# Main.net
KiCad netlist of a schematic drawn in Altium Designer
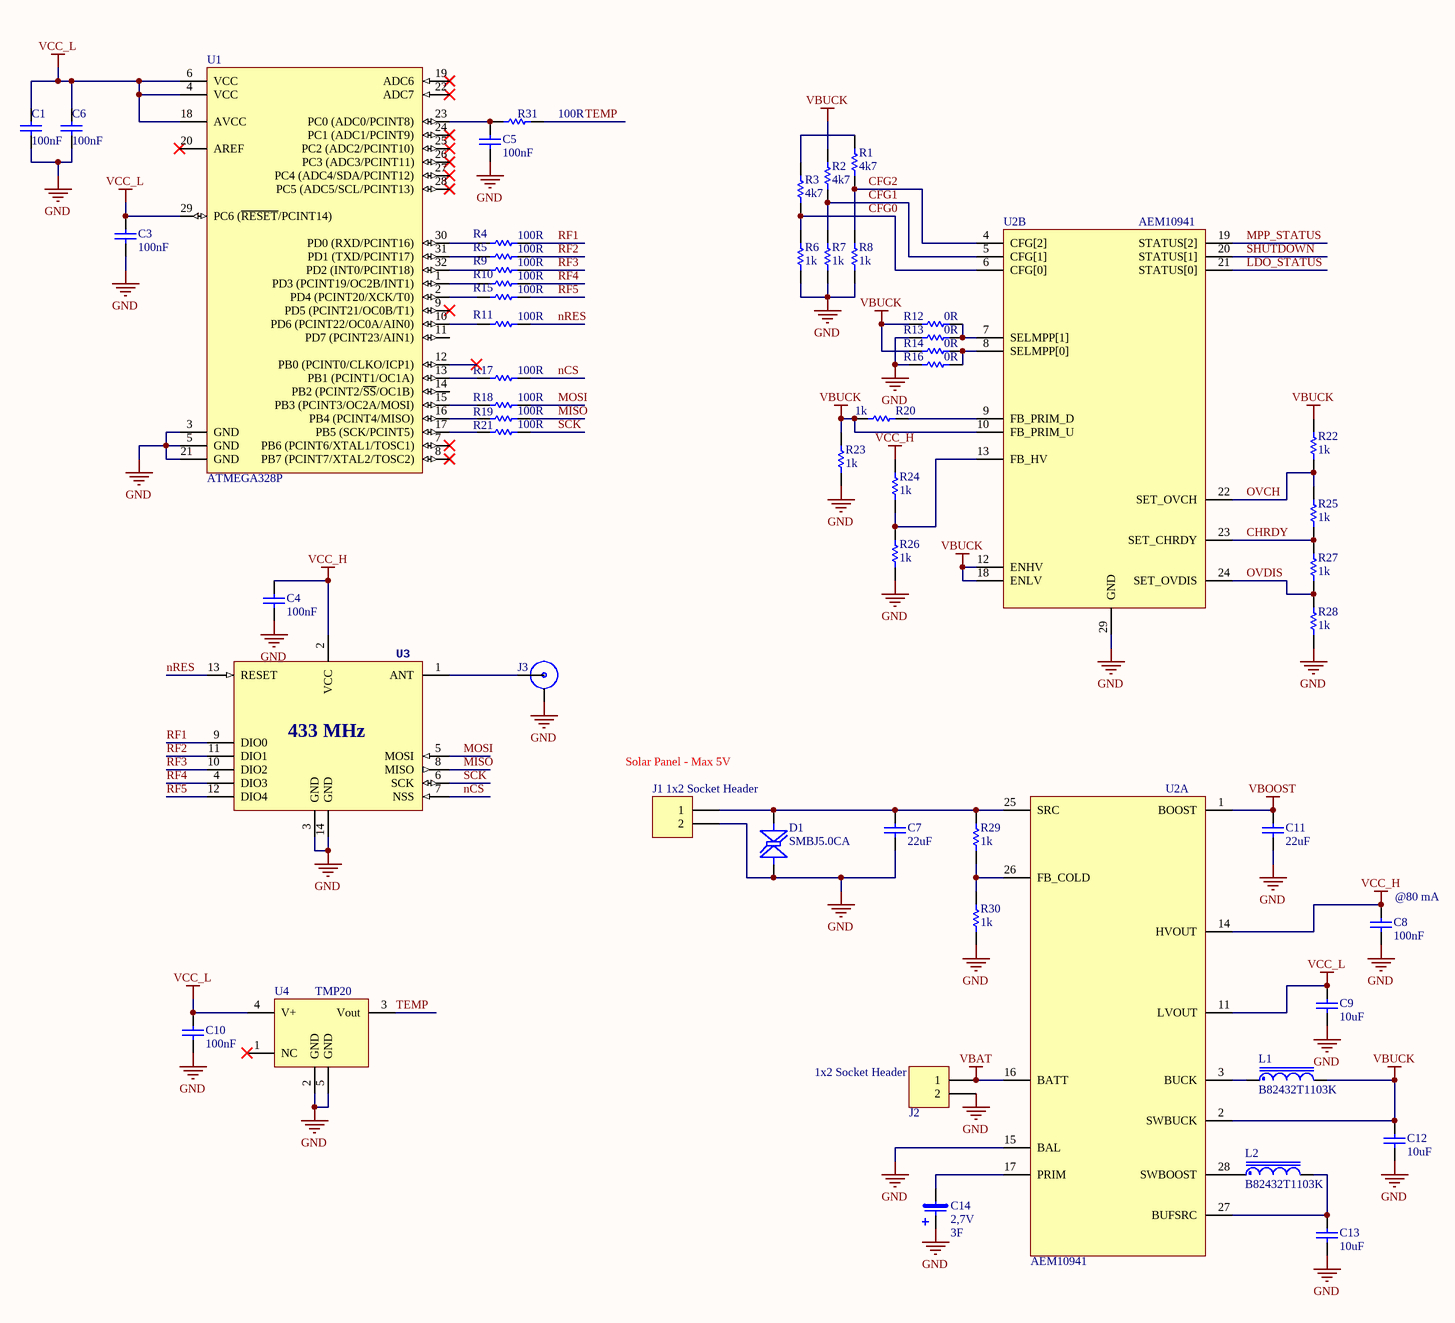
[diagram p0: Main.SchDoc]

(export (version "E")
  (design (tool "Eeschema 10.0.6"))
  (components
    (comp (ref "C1")
      (value "100nF")
      (footprint "C0603")
      (description "Capacitor SMD")
      (fields (field (name "VOLTAGE") "16V") (field (name "PART NUMBER") "C0603_100nF_16V_±10%"))
      (libsource (lib "Pasives_Capacitor_SMD") (part "Capacitor"))
    )
    (comp (ref "C3")
      (value "100nF")
      (footprint "C0603")
      (description "Capacitor SMD")
      (fields (field (name "VOLTAGE") "16V") (field (name "PART NUMBER") "C0603_100nF_16V_±10%"))
      (libsource (lib "Pasives_Capacitor_SMD") (part "Capacitor"))
    )
    (comp (ref "C4")
      (value "100nF")
      (footprint "C0603")
      (description "Capacitor SMD")
      (fields (field (name "VOLTAGE") "16V") (field (name "PART NUMBER") "C0603_100nF_16V_±10%"))
      (libsource (lib "Pasives_Capacitor_SMD") (part "Capacitor"))
    )
    (comp (ref "C5")
      (value "100nF")
      (footprint "C0603")
      (description "Capacitor SMD")
      (fields (field (name "VOLTAGE") "16V") (field (name "PART NUMBER") "C0603_100nF_16V_±10%"))
      (libsource (lib "Pasives_Capacitor_SMD") (part "Capacitor"))
    )
    (comp (ref "C6")
      (value "100nF")
      (footprint "C0603")
      (description "Capacitor SMD")
      (fields (field (name "VOLTAGE") "16V") (field (name "PART NUMBER") "C0603_100nF_16V_±10%"))
      (libsource (lib "Pasives_Capacitor_SMD") (part "Capacitor"))
    )
    (comp (ref "C7")
      (value "22uF")
      (footprint "C1206")
      (description "Capacitor SMD")
      (fields (field (name "VOLTAGE") "10V") (field (name "PART NUMBER") "C1206_22uF_10V_±10%"))
      (libsource (lib "Pasives_Capacitor_SMD") (part "Capacitor"))
    )
    (comp (ref "C8")
      (value "100nF")
      (footprint "C0603")
      (description "Capacitor SMD")
      (fields (field (name "VOLTAGE") "16V") (field (name "PART NUMBER") "C0603_100nF_16V_±10%"))
      (libsource (lib "Pasives_Capacitor_SMD") (part "Capacitor"))
    )
    (comp (ref "C9")
      (value "10uF")
      (footprint "C1206")
      (description "Capacitor SMD")
      (fields (field (name "VOLTAGE") "25V") (field (name "PART NUMBER") "C1206_10uF_25V_±10%"))
      (libsource (lib "Pasives_Capacitor_SMD") (part "Capacitor"))
    )
    (comp (ref "C10")
      (value "100nF")
      (footprint "C0603")
      (description "Capacitor SMD")
      (fields (field (name "VOLTAGE") "16V") (field (name "PART NUMBER") "C0603_100nF_16V_±10%"))
      (libsource (lib "Pasives_Capacitor_SMD") (part "Capacitor"))
    )
    (comp (ref "C11")
      (value "22uF")
      (footprint "C1206")
      (description "Capacitor SMD")
      (fields (field (name "VOLTAGE") "25V") (field (name "PART NUMBER") "C1206_22uF_25V_±10%"))
      (libsource (lib "Pasives_Capacitor_SMD") (part "Capacitor"))
    )
    (comp (ref "C12")
      (value "10uF")
      (footprint "C1210")
      (description "Capacitor SMD")
      (fields (field (name "VOLTAGE") "50V") (field (name "PART NUMBER") "C1210_10uF_50V_±10%"))
      (libsource (lib "Pasives_Capacitor_SMD") (part "Capacitor"))
    )
    (comp (ref "C13")
      (value "10uF")
      (footprint "C1210")
      (description "Capacitor SMD")
      (fields (field (name "VOLTAGE") "50V") (field (name "PART NUMBER") "C1210_10uF_50V_±10%"))
      (libsource (lib "Pasives_Capacitor_SMD") (part "Capacitor"))
    )
    (comp (ref "C14")
      (value "Electrolytic")
      (footprint "WCAP-STSC_D8xH20mm")
      (description "Capacitor, Electrolytic, THT")
      (fields
        (field (name "VOLTAGE") "2,7V")
        (field (name "CAPACITANCE") "3F")
        (field (name "PART NUMBER") "850617030001")
        (field (name "MANUFACTURER") "Wurth")
      )
      (libsource (lib "Pasives_Electrolytic_THT") (part "Electrolytic"))
    )
    (comp (ref "D1")
      (value "SMBJ5.0CA")
      (footprint "DO-214AA")
      (description "Protection, Bidirectional Transient Suppression Diodes")
      (fields (field (name "PART NUMBER") "TVS Bidir 5Vdc") (field (name "VOLTAGE") "5Vdc"))
      (libsource (lib "Protection") (part "Zener_Bidir_TVS"))
    )
    (comp (ref "J1")
      (value "1x2 Socket Header")
      (footprint "MOLEX 22-05-7025")
      (description "Connector, 2 pin Socket Header")
      (fields (field (name "PART NUMBER") "Molex - 2 pin") (field (name "MANUFACTURER") "Molex"))
      (libsource (lib "Connectors_Power") (part "1x2 Socket Header"))
    )
    (comp (ref "J2")
      (value "1x2 Socket Header")
      (footprint "MOLEX 22-05-7025")
      (description "Connector, 2 pin Socket Header")
      (fields (field (name "PART NUMBER") "Molex - 2 pin") (field (name "MANUFACTURER") "Molex"))
      (libsource (lib "Connectors_Power") (part "1x2 Socket Header"))
    )
    (comp (ref "J3")
      (value "132322")
      (footprint "SMA_Edge_132322")
      (description "Coax")
      (fields (field (name "PART NUMBER") "SMA_Edge_132322") (field (name "MANUFACTURER") "FCI Amphenol"))
      (libsource (lib "Connectors_Antenna") (part "Coax"))
    )
    (comp (ref "L1")
      (value "B82432T1103K")
      (footprint "L1812-T")
      (description "Inductor, Power, SMD")
      (fields (field (name "PART NUMBER") "10uH_0,650A") (field (name "MANUFACTURER") "Epcos"))
      (libsource (lib "Pasivos_Inductor_SMD") (part "Power Inductor"))
    )
    (comp (ref "L2")
      (value "B82432T1103K")
      (footprint "L1812-T")
      (description "Inductor, Power, SMD")
      (fields (field (name "PART NUMBER") "10uH_0,650A") (field (name "MANUFACTURER") "Epcos"))
      (libsource (lib "Pasivos_Inductor_SMD") (part "Power Inductor"))
    )
    (comp (ref "R1")
      (value "4k7")
      (footprint "R0603")
      (description "Resistor, SMD")
      (fields (field (name "TOLERANCE") "±1%") (field (name "POWER") "0.1W"))
      (libsource (lib "Pasives_Resistor_SMD") (part "Resistor"))
    )
    (comp (ref "R2")
      (value "4k7")
      (footprint "R0603")
      (description "Resistor, SMD")
      (fields (field (name "TOLERANCE") "±1%") (field (name "POWER") "0.1W"))
      (libsource (lib "Pasives_Resistor_SMD") (part "Resistor"))
    )
    (comp (ref "R3")
      (value "4k7")
      (footprint "R0603")
      (description "Resistor, SMD")
      (fields (field (name "TOLERANCE") "±1%") (field (name "POWER") "0.1W"))
      (libsource (lib "Pasives_Resistor_SMD") (part "Resistor"))
    )
    (comp (ref "R4")
      (value "100R")
      (footprint "R0603")
      (description "Resistor, SMD")
      (fields (field (name "TOLERANCE") "±1%") (field (name "POWER") "0.1W"))
      (libsource (lib "Pasives_Resistor_SMD") (part "Resistor"))
    )
    (comp (ref "R5")
      (value "100R")
      (footprint "R0603")
      (description "Resistor, SMD")
      (fields (field (name "TOLERANCE") "±1%") (field (name "POWER") "0.1W"))
      (libsource (lib "Pasives_Resistor_SMD") (part "Resistor"))
    )
    (comp (ref "R6")
      (value "1k")
      (footprint "R0603")
      (description "Resistor, SMD")
      (fields (field (name "TOLERANCE") "±1%") (field (name "POWER") "0.1W"))
      (libsource (lib "Pasives_Resistor_SMD") (part "Resistor"))
    )
    (comp (ref "R7")
      (value "1k")
      (footprint "R0603")
      (description "Resistor, SMD")
      (fields (field (name "TOLERANCE") "±1%") (field (name "POWER") "0.1W"))
      (libsource (lib "Pasives_Resistor_SMD") (part "Resistor"))
    )
    (comp (ref "R8")
      (value "1k")
      (footprint "R0603")
      (description "Resistor, SMD")
      (fields (field (name "TOLERANCE") "±1%") (field (name "POWER") "0.1W"))
      (libsource (lib "Pasives_Resistor_SMD") (part "Resistor"))
    )
    (comp (ref "R9")
      (value "100R")
      (footprint "R0603")
      (description "Resistor, SMD")
      (fields (field (name "TOLERANCE") "±1%") (field (name "POWER") "0.1W"))
      (libsource (lib "Pasives_Resistor_SMD") (part "Resistor"))
    )
    (comp (ref "R10")
      (value "100R")
      (footprint "R0603")
      (description "Resistor, SMD")
      (fields (field (name "TOLERANCE") "±1%") (field (name "POWER") "0.1W"))
      (libsource (lib "Pasives_Resistor_SMD") (part "Resistor"))
    )
    (comp (ref "R11")
      (value "100R")
      (footprint "R0603")
      (description "Resistor, SMD")
      (fields (field (name "TOLERANCE") "±1%") (field (name "POWER") "0.1W"))
      (libsource (lib "Pasives_Resistor_SMD") (part "Resistor"))
    )
    (comp (ref "R12")
      (value "0R")
      (footprint "R0603")
      (description "Resistor, SMD")
      (fields (field (name "TOLERANCE") "±5%") (field (name "POWER") "0.1W"))
      (libsource (lib "Pasives_Resistor_SMD") (part "Resistor"))
    )
    (comp (ref "R13")
      (value "0R")
      (footprint "R0603")
      (description "Resistor, SMD")
      (fields (field (name "TOLERANCE") "±5%") (field (name "POWER") "0.1W"))
      (libsource (lib "Pasives_Resistor_SMD") (part "Resistor"))
    )
    (comp (ref "R14")
      (value "0R")
      (footprint "R0603")
      (description "Resistor, SMD")
      (fields (field (name "TOLERANCE") "±5%") (field (name "POWER") "0.1W"))
      (libsource (lib "Pasives_Resistor_SMD") (part "Resistor"))
    )
    (comp (ref "R15")
      (value "100R")
      (footprint "R0603")
      (description "Resistor, SMD")
      (fields (field (name "TOLERANCE") "±1%") (field (name "POWER") "0.1W"))
      (libsource (lib "Pasives_Resistor_SMD") (part "Resistor"))
    )
    (comp (ref "R16")
      (value "0R")
      (footprint "R0603")
      (description "Resistor, SMD")
      (fields (field (name "TOLERANCE") "±5%") (field (name "POWER") "0.1W"))
      (libsource (lib "Pasives_Resistor_SMD") (part "Resistor"))
    )
    (comp (ref "R17")
      (value "100R")
      (footprint "R0603")
      (description "Resistor, SMD")
      (fields (field (name "TOLERANCE") "±1%") (field (name "POWER") "0.1W"))
      (libsource (lib "Pasives_Resistor_SMD") (part "Resistor"))
    )
    (comp (ref "R18")
      (value "100R")
      (footprint "R0603")
      (description "Resistor, SMD")
      (fields (field (name "TOLERANCE") "±1%") (field (name "POWER") "0.1W"))
      (libsource (lib "Pasives_Resistor_SMD") (part "Resistor"))
    )
    (comp (ref "R19")
      (value "100R")
      (footprint "R0603")
      (description "Resistor, SMD")
      (fields (field (name "TOLERANCE") "±1%") (field (name "POWER") "0.1W"))
      (libsource (lib "Pasives_Resistor_SMD") (part "Resistor"))
    )
    (comp (ref "R20")
      (value "1k")
      (footprint "R0603")
      (description "Resistor, SMD")
      (fields (field (name "TOLERANCE") "±1%") (field (name "POWER") "0.1W"))
      (libsource (lib "Pasives_Resistor_SMD") (part "Resistor"))
    )
    (comp (ref "R21")
      (value "100R")
      (footprint "R0603")
      (description "Resistor, SMD")
      (fields (field (name "TOLERANCE") "±1%") (field (name "POWER") "0.1W"))
      (libsource (lib "Pasives_Resistor_SMD") (part "Resistor"))
    )
    (comp (ref "R22")
      (value "1k")
      (footprint "R0603")
      (description "Resistor, SMD")
      (fields (field (name "TOLERANCE") "±1%") (field (name "POWER") "0.1W"))
      (libsource (lib "Pasives_Resistor_SMD") (part "Resistor"))
    )
    (comp (ref "R23")
      (value "1k")
      (footprint "R0603")
      (description "Resistor, SMD")
      (fields (field (name "TOLERANCE") "±1%") (field (name "POWER") "0.1W"))
      (libsource (lib "Pasives_Resistor_SMD") (part "Resistor"))
    )
    (comp (ref "R24")
      (value "1k")
      (footprint "R0603")
      (description "Resistor, SMD")
      (fields (field (name "TOLERANCE") "±1%") (field (name "POWER") "0.1W"))
      (libsource (lib "Pasives_Resistor_SMD") (part "Resistor"))
    )
    (comp (ref "R25")
      (value "1k")
      (footprint "R0603")
      (description "Resistor, SMD")
      (fields (field (name "TOLERANCE") "±1%") (field (name "POWER") "0.1W"))
      (libsource (lib "Pasives_Resistor_SMD") (part "Resistor"))
    )
    (comp (ref "R26")
      (value "1k")
      (footprint "R0603")
      (description "Resistor, SMD")
      (fields (field (name "TOLERANCE") "±1%") (field (name "POWER") "0.1W"))
      (libsource (lib "Pasives_Resistor_SMD") (part "Resistor"))
    )
    (comp (ref "R27")
      (value "1k")
      (footprint "R0603")
      (description "Resistor, SMD")
      (fields (field (name "TOLERANCE") "±1%") (field (name "POWER") "0.1W"))
      (libsource (lib "Pasives_Resistor_SMD") (part "Resistor"))
    )
    (comp (ref "R28")
      (value "1k")
      (footprint "R0603")
      (description "Resistor, SMD")
      (fields (field (name "TOLERANCE") "±1%") (field (name "POWER") "0.1W"))
      (libsource (lib "Pasives_Resistor_SMD") (part "Resistor"))
    )
    (comp (ref "R29")
      (value "1k")
      (footprint "R0603")
      (description "Resistor, SMD")
      (fields (field (name "TOLERANCE") "±1%") (field (name "POWER") "0.1W"))
      (libsource (lib "Pasives_Resistor_SMD") (part "Resistor"))
    )
    (comp (ref "R30")
      (value "1k")
      (footprint "R0603")
      (description "Resistor, SMD")
      (fields (field (name "TOLERANCE") "±1%") (field (name "POWER") "0.1W"))
      (libsource (lib "Pasives_Resistor_SMD") (part "Resistor"))
    )
    (comp (ref "R31")
      (value "100R")
      (footprint "R0603")
      (description "Resistor, SMD")
      (fields (field (name "TOLERANCE") "±1%") (field (name "POWER") "0.1W"))
      (libsource (lib "Pasives_Resistor_SMD") (part "Resistor"))
    )
    (comp (ref "U1")
      (value "ATMEGA328P")
      (footprint "QFN32")
      (description "Processor, 8-bit AVR Microcontroller")
      (fields (field (name "PART NUMBER") "ATMEGA328P-QFN") (field (name "MANUFACTURER") "Atmel"))
      (libsource (lib "Processor") (part "ATMEGA328P"))
    )
    (comp (ref "U2")
      (value "AEM10941")
      (footprint "QFN28")
      (fields (field (name "MANUFACTURER") "E-PEAS"))
      (libsource (lib "Power") (part "AEM10941"))
    )
    (comp (ref "U3")
      (value "433 MHz")
      (footprint "RFM69CW")
      (description "RFM69CW SMD Wireless Transceiver - 433 MHz")
      (fields (field (name "PART NUMBER") "RFM69CW"))
      (libsource (lib "RF") (part "RFM69CW"))
    )
    (comp (ref "U4")
      (value "TMP20")
      (footprint "SOT-563")
      (description "TMP20 ±2.5°C Low-Power, Analog Out Temperature Sensor")
      (fields (field (name "MANUFACTURER") "Texas Instruments"))
      (libsource (lib "Sensors") (part "TMP20"))
    )
  )
  (nets
    (net (code "1") (name "/CFG0") (class "Default")
      (node (ref "R3") (pin "1") (pinfunction "1_1") (pintype "passive"))
      (node (ref "R6") (pin "2") (pinfunction "2_2") (pintype "passive"))
      (node (ref "U2") (pin "6") (pinfunction "CFG[0]_6") (pintype "passive"))
    )
    (net (code "2") (name "/CFG1") (class "Default")
      (node (ref "R2") (pin "1") (pinfunction "1_1") (pintype "passive"))
      (node (ref "R7") (pin "2") (pinfunction "2_2") (pintype "passive"))
      (node (ref "U2") (pin "5") (pinfunction "CFG[1]_5") (pintype "passive"))
    )
    (net (code "3") (name "/CFG2") (class "Default")
      (node (ref "R1") (pin "1") (pinfunction "1_1") (pintype "passive"))
      (node (ref "R8") (pin "2") (pinfunction "2_2") (pintype "passive"))
      (node (ref "U2") (pin "4") (pinfunction "CFG[2]_4") (pintype "passive"))
    )
    (net (code "4") (name "/CHRDY") (class "Default")
      (node (ref "R25") (pin "1") (pinfunction "1_1") (pintype "passive"))
      (node (ref "R27") (pin "2") (pinfunction "2_2") (pintype "passive"))
      (node (ref "U2") (pin "23") (pinfunction "SET_CHRDY_23") (pintype "passive"))
    )
    (net (code "5") (name "/LDO_STATUS") (class "Default")
      (node (ref "U2") (pin "21") (pinfunction "STATUS[0]_21") (pintype "passive"))
    )
    (net (code "6") (name "/MISO") (class "Default")
      (node (ref "R19") (pin "2") (pinfunction "2_2") (pintype "passive"))
      (node (ref "U3") (pin "8") (pinfunction "MISO_8") (pintype "output"))
    )
    (net (code "7") (name "/MOSI") (class "Default")
      (node (ref "R18") (pin "2") (pinfunction "2_2") (pintype "passive"))
      (node (ref "U3") (pin "5") (pinfunction "MOSI_5") (pintype "input"))
    )
    (net (code "8") (name "/MPP_STATUS") (class "Default")
      (node (ref "U2") (pin "19") (pinfunction "STATUS[2]_19") (pintype "passive"))
    )
    (net (code "9") (name "/OVCH") (class "Default")
      (node (ref "R22") (pin "1") (pinfunction "1_1") (pintype "passive"))
      (node (ref "R25") (pin "2") (pinfunction "2_2") (pintype "passive"))
      (node (ref "U2") (pin "22") (pinfunction "SET_OVCH_22") (pintype "passive"))
    )
    (net (code "10") (name "/OVDIS") (class "Default")
      (node (ref "R27") (pin "1") (pinfunction "1_1") (pintype "passive"))
      (node (ref "R28") (pin "2") (pinfunction "2_2") (pintype "passive"))
      (node (ref "U2") (pin "24") (pinfunction "SET_OVDIS_24") (pintype "passive"))
    )
    (net (code "11") (name "/RF1") (class "Default")
      (node (ref "R4") (pin "2") (pinfunction "2_2") (pintype "passive"))
      (node (ref "U3") (pin "9") (pinfunction "DIO0_9") (pintype "passive"))
    )
    (net (code "12") (name "/RF2") (class "Default")
      (node (ref "R5") (pin "2") (pinfunction "2_2") (pintype "passive"))
      (node (ref "U3") (pin "11") (pinfunction "DIO1_11") (pintype "passive"))
    )
    (net (code "13") (name "/RF3") (class "Default")
      (node (ref "R9") (pin "2") (pinfunction "2_2") (pintype "passive"))
      (node (ref "U3") (pin "10") (pinfunction "DIO2_10") (pintype "passive"))
    )
    (net (code "14") (name "/RF4") (class "Default")
      (node (ref "R10") (pin "2") (pinfunction "2_2") (pintype "passive"))
      (node (ref "U3") (pin "4") (pinfunction "DIO3_4") (pintype "passive"))
    )
    (net (code "15") (name "/RF5") (class "Default")
      (node (ref "R15") (pin "2") (pinfunction "2_2") (pintype "passive"))
      (node (ref "U3") (pin "12") (pinfunction "DIO4_12") (pintype "passive"))
    )
    (net (code "16") (name "/SCK") (class "Default")
      (node (ref "R21") (pin "2") (pinfunction "2_2") (pintype "passive"))
      (node (ref "U3") (pin "6") (pinfunction "SCK_6") (pintype "bidirectional"))
    )
    (net (code "17") (name "/SHUTDOWN") (class "Default")
      (node (ref "U2") (pin "20") (pinfunction "STATUS[1]_20") (pintype "passive"))
    )
    (net (code "18") (name "/TEMP") (class "Default")
      (node (ref "R31") (pin "2") (pinfunction "2_2") (pintype "passive"))
      (node (ref "U4") (pin "3") (pinfunction "Vout_3") (pintype "passive"))
    )
    (net (code "19") (name "/nCS") (class "Default")
      (node (ref "R17") (pin "2") (pinfunction "2_2") (pintype "passive"))
      (node (ref "U3") (pin "7") (pinfunction "NSS_7") (pintype "input"))
    )
    (net (code "20") (name "/nRES") (class "Default")
      (node (ref "R11") (pin "2") (pinfunction "2_2") (pintype "passive"))
      (node (ref "U3") (pin "13") (pinfunction "RESET_13") (pintype "input"))
    )
    (net (code "21") (name "GND") (class "Default")
      (node (ref "C1") (pin "1") (pinfunction "1_1") (pintype "passive"))
      (node (ref "C10") (pin "1") (pinfunction "1_1") (pintype "passive"))
      (node (ref "C11") (pin "1") (pinfunction "1_1") (pintype "passive"))
      (node (ref "C12") (pin "1") (pinfunction "1_1") (pintype "passive"))
      (node (ref "C13") (pin "1") (pinfunction "1_1") (pintype "passive"))
      (node (ref "C14") (pin "1") (pinfunction "1_1") (pintype "passive"))
      (node (ref "C3") (pin "1") (pinfunction "1_1") (pintype "passive"))
      (node (ref "C4") (pin "1") (pinfunction "1_1") (pintype "passive"))
      (node (ref "C5") (pin "1") (pinfunction "1_1") (pintype "passive"))
      (node (ref "C6") (pin "1") (pinfunction "1_1") (pintype "passive"))
      (node (ref "C7") (pin "1") (pinfunction "1_1") (pintype "passive"))
      (node (ref "C8") (pin "1") (pinfunction "1_1") (pintype "passive"))
      (node (ref "C9") (pin "1") (pinfunction "1_1") (pintype "passive"))
      (node (ref "D1") (pin "A") (pinfunction "A_A") (pintype "passive"))
      (node (ref "J1") (pin "2") (pinfunction "2_2") (pintype "passive"))
      (node (ref "J2") (pin "2") (pinfunction "2_2") (pintype "passive"))
      (node (ref "J3") (pin "G") (pinfunction "G_G") (pintype "passive"))
      (node (ref "R13") (pin "1") (pinfunction "1_1") (pintype "passive"))
      (node (ref "R16") (pin "1") (pinfunction "1_1") (pintype "passive"))
      (node (ref "R23") (pin "2") (pinfunction "2_2") (pintype "passive"))
      (node (ref "R26") (pin "2") (pinfunction "2_2") (pintype "passive"))
      (node (ref "R28") (pin "1") (pinfunction "1_1") (pintype "passive"))
      (node (ref "R30") (pin "1") (pinfunction "1_1") (pintype "passive"))
      (node (ref "R6") (pin "1") (pinfunction "1_1") (pintype "passive"))
      (node (ref "R7") (pin "1") (pinfunction "1_1") (pintype "passive"))
      (node (ref "R8") (pin "1") (pinfunction "1_1") (pintype "passive"))
      (node (ref "U1") (pin "21") (pinfunction "GND_21") (pintype "power_in"))
      (node (ref "U1") (pin "3") (pinfunction "GND_3") (pintype "power_in"))
      (node (ref "U1") (pin "5") (pinfunction "GND_5") (pintype "power_in"))
      (node (ref "U2") (pin "15") (pinfunction "BAL_15") (pintype "passive"))
      (node (ref "U2") (pin "29") (pinfunction "GND_29") (pintype "passive"))
      (node (ref "U3") (pin "14") (pinfunction "GND_14") (pintype "passive"))
      (node (ref "U3") (pin "3") (pinfunction "GND_3") (pintype "passive"))
      (node (ref "U4") (pin "2") (pinfunction "GND_2") (pintype "passive"))
      (node (ref "U4") (pin "5") (pinfunction "GND_5") (pintype "passive"))
    )
    (net (code "22") (name "Net-(R1-Pad2)") (class "Default")
      (node (ref "R1") (pin "2") (pinfunction "2_2") (pintype "passive"))
      (node (ref "R3") (pin "2") (pinfunction "2_2") (pintype "passive"))
    )
    (net (code "23") (name "Net-(U1-PB1_(PCINT1{slash}OC1A))") (class "Default")
      (node (ref "R17") (pin "1") (pinfunction "1_1") (pintype "passive"))
      (node (ref "U1") (pin "13") (pinfunction "PB1_(PCINT1/OC1A)_13") (pintype "bidirectional"))
    )
    (net (code "24") (name "Net-(U1-PB3_(PCINT3{slash}OC2A{slash}MOSI))") (class "Default")
      (node (ref "R18") (pin "1") (pinfunction "1_1") (pintype "passive"))
      (node (ref "U1") (pin "15") (pinfunction "PB3_(PCINT3/OC2A/MOSI)_15") (pintype "bidirectional"))
    )
    (net (code "25") (name "Net-(U1-PB4_(PCINT4{slash}MISO))") (class "Default")
      (node (ref "R19") (pin "1") (pinfunction "1_1") (pintype "passive"))
      (node (ref "U1") (pin "16") (pinfunction "PB4_(PCINT4/MISO)_16") (pintype "bidirectional"))
    )
    (net (code "26") (name "Net-(U1-PB5_(SCK{slash}PCINT5))") (class "Default")
      (node (ref "R21") (pin "1") (pinfunction "1_1") (pintype "passive"))
      (node (ref "U1") (pin "17") (pinfunction "PB5_(SCK/PCINT5)_17") (pintype "bidirectional"))
    )
    (net (code "27") (name "Net-(U1-PC0_(ADC0{slash}PCINT8))") (class "Default")
      (node (ref "C5") (pin "2") (pinfunction "2_2") (pintype "passive"))
      (node (ref "R31") (pin "1") (pinfunction "1_1") (pintype "passive"))
      (node (ref "U1") (pin "23") (pinfunction "PC0_(ADC0/PCINT8)_23") (pintype "bidirectional"))
    )
    (net (code "28") (name "Net-(U1-PD0_(RXD{slash}PCINT16))") (class "Default")
      (node (ref "R4") (pin "1") (pinfunction "1_1") (pintype "passive"))
      (node (ref "U1") (pin "30") (pinfunction "PD0_(RXD/PCINT16)_30") (pintype "bidirectional"))
    )
    (net (code "29") (name "Net-(U1-PD1_(TXD{slash}PCINT17))") (class "Default")
      (node (ref "R5") (pin "1") (pinfunction "1_1") (pintype "passive"))
      (node (ref "U1") (pin "31") (pinfunction "PD1_(TXD/PCINT17)_31") (pintype "bidirectional"))
    )
    (net (code "30") (name "Net-(U1-PD2_(INT0{slash}PCINT18))") (class "Default")
      (node (ref "R9") (pin "1") (pinfunction "1_1") (pintype "passive"))
      (node (ref "U1") (pin "32") (pinfunction "PD2_(INT0/PCINT18)_32") (pintype "bidirectional"))
    )
    (net (code "31") (name "Net-(U1-PD3_(PCINT19{slash}OC2B{slash}INT1))") (class "Default")
      (node (ref "R10") (pin "1") (pinfunction "1_1") (pintype "passive"))
      (node (ref "U1") (pin "1") (pinfunction "PD3_(PCINT19/OC2B/INT1)_1") (pintype "bidirectional"))
    )
    (net (code "32") (name "Net-(U1-PD4_(PCINT20{slash}XCK{slash}T0))") (class "Default")
      (node (ref "R15") (pin "1") (pinfunction "1_1") (pintype "passive"))
      (node (ref "U1") (pin "2") (pinfunction "PD4_(PCINT20/XCK/T0)_2") (pintype "bidirectional"))
    )
    (net (code "33") (name "Net-(U1-PD6_(PCINT22{slash}OC0A{slash}AIN0))") (class "Default")
      (node (ref "R11") (pin "1") (pinfunction "1_1") (pintype "passive"))
      (node (ref "U1") (pin "10") (pinfunction "PD6_(PCINT22/OC0A/AIN0)_10") (pintype "bidirectional"))
    )
    (net (code "34") (name "Net-(U2A-BUCK)") (class "Default")
      (node (ref "L1") (pin "1") (pinfunction "1_1") (pintype "passive"))
      (node (ref "U2") (pin "3") (pinfunction "BUCK_3") (pintype "passive"))
    )
    (net (code "35") (name "Net-(U2A-BUFSRC)") (class "Default")
      (node (ref "C13") (pin "2") (pinfunction "2_2") (pintype "passive"))
      (node (ref "L2") (pin "2") (pinfunction "2_2") (pintype "passive"))
      (node (ref "U2") (pin "27") (pinfunction "BUFSRC_27") (pintype "passive"))
    )
    (net (code "36") (name "Net-(U2A-FB_COLD)") (class "Default")
      (node (ref "R29") (pin "1") (pinfunction "1_1") (pintype "passive"))
      (node (ref "R30") (pin "2") (pinfunction "2_2") (pintype "passive"))
      (node (ref "U2") (pin "26") (pinfunction "FB_COLD_26") (pintype "passive"))
    )
    (net (code "37") (name "Net-(U2A-PRIM)") (class "Default")
      (node (ref "C14") (pin "2") (pinfunction "2_2") (pintype "passive"))
      (node (ref "U2") (pin "17") (pinfunction "PRIM_17") (pintype "passive"))
    )
    (net (code "38") (name "Net-(U2A-SRC)") (class "Default")
      (node (ref "C7") (pin "2") (pinfunction "2_2") (pintype "passive"))
      (node (ref "D1") (pin "K") (pinfunction "K_K") (pintype "passive"))
      (node (ref "J1") (pin "1") (pinfunction "1_1") (pintype "passive"))
      (node (ref "R29") (pin "2") (pinfunction "2_2") (pintype "passive"))
      (node (ref "U2") (pin "25") (pinfunction "SRC_25") (pintype "passive"))
    )
    (net (code "39") (name "Net-(U2A-SWBOOST)") (class "Default")
      (node (ref "L2") (pin "1") (pinfunction "1_1") (pintype "passive"))
      (node (ref "U2") (pin "28") (pinfunction "SWBOOST_28") (pintype "passive"))
    )
    (net (code "40") (name "Net-(U2B-FB_HV)") (class "Default")
      (node (ref "R24") (pin "2") (pinfunction "2_2") (pintype "passive"))
      (node (ref "R26") (pin "1") (pinfunction "1_1") (pintype "passive"))
      (node (ref "U2") (pin "13") (pinfunction "FB_HV_13") (pintype "passive"))
    )
    (net (code "41") (name "Net-(U2B-FB_PRIM_D)") (class "Default")
      (node (ref "R20") (pin "1") (pinfunction "1_1") (pintype "passive"))
      (node (ref "U2") (pin "9") (pinfunction "FB_PRIM_D_9") (pintype "passive"))
    )
    (net (code "42") (name "Net-(U2B-SELMPP[0])") (class "Default")
      (node (ref "R14") (pin "2") (pinfunction "2_2") (pintype "passive"))
      (node (ref "R16") (pin "2") (pinfunction "2_2") (pintype "passive"))
      (node (ref "U2") (pin "8") (pinfunction "SELMPP[0]_8") (pintype "passive"))
    )
    (net (code "43") (name "Net-(U2B-SELMPP[1])") (class "Default")
      (node (ref "R12") (pin "2") (pinfunction "2_2") (pintype "passive"))
      (node (ref "R13") (pin "2") (pinfunction "2_2") (pintype "passive"))
      (node (ref "U2") (pin "7") (pinfunction "SELMPP[1]_7") (pintype "passive"))
    )
    (net (code "44") (name "Net-(U3-ANT)") (class "Default")
      (node (ref "J3") (pin "1") (pinfunction "1_1") (pintype "passive"))
      (node (ref "U3") (pin "1") (pinfunction "ANT_1") (pintype "passive"))
    )
    (net (code "45") (name "VBAT") (class "Default")
      (node (ref "J2") (pin "1") (pinfunction "1_1") (pintype "passive"))
      (node (ref "U2") (pin "16") (pinfunction "BATT_16") (pintype "passive"))
    )
    (net (code "46") (name "VBOOST") (class "Default")
      (node (ref "C11") (pin "2") (pinfunction "2_2") (pintype "passive"))
      (node (ref "U2") (pin "1") (pinfunction "BOOST_1") (pintype "passive"))
    )
    (net (code "47") (name "VBUCK") (class "Default")
      (node (ref "C12") (pin "2") (pinfunction "2_2") (pintype "passive"))
      (node (ref "L1") (pin "2") (pinfunction "2_2") (pintype "passive"))
      (node (ref "R12") (pin "1") (pinfunction "1_1") (pintype "passive"))
      (node (ref "R14") (pin "1") (pinfunction "1_1") (pintype "passive"))
      (node (ref "R2") (pin "2") (pinfunction "2_2") (pintype "passive"))
      (node (ref "R20") (pin "2") (pinfunction "2_2") (pintype "passive"))
      (node (ref "R22") (pin "2") (pinfunction "2_2") (pintype "passive"))
      (node (ref "R23") (pin "1") (pinfunction "1_1") (pintype "passive"))
      (node (ref "U2") (pin "10") (pinfunction "FB_PRIM_U_10") (pintype "passive"))
      (node (ref "U2") (pin "12") (pinfunction "ENHV_12") (pintype "passive"))
      (node (ref "U2") (pin "18") (pinfunction "ENLV_18") (pintype "passive"))
      (node (ref "U2") (pin "2") (pinfunction "SWBUCK_2") (pintype "passive"))
    )
    (net (code "48") (name "VCC_H") (class "Default")
      (node (ref "C4") (pin "2") (pinfunction "2_2") (pintype "passive"))
      (node (ref "C8") (pin "2") (pinfunction "2_2") (pintype "passive"))
      (node (ref "R24") (pin "1") (pinfunction "1_1") (pintype "passive"))
      (node (ref "U2") (pin "14") (pinfunction "HVOUT_14") (pintype "passive"))
      (node (ref "U3") (pin "2") (pinfunction "VCC_2") (pintype "passive"))
    )
    (net (code "49") (name "VCC_L") (class "Default")
      (node (ref "C1") (pin "2") (pinfunction "2_2") (pintype "passive"))
      (node (ref "C10") (pin "2") (pinfunction "2_2") (pintype "passive"))
      (node (ref "C3") (pin "2") (pinfunction "2_2") (pintype "passive"))
      (node (ref "C6") (pin "2") (pinfunction "2_2") (pintype "passive"))
      (node (ref "C9") (pin "2") (pinfunction "2_2") (pintype "passive"))
      (node (ref "U1") (pin "18") (pinfunction "AVCC_18") (pintype "power_in"))
      (node (ref "U1") (pin "29") (pinfunction "PC6_(~{RESET}/PCINT14)_29") (pintype "bidirectional"))
      (node (ref "U1") (pin "4") (pinfunction "VCC_4") (pintype "power_in"))
      (node (ref "U1") (pin "6") (pinfunction "VCC_6") (pintype "power_in"))
      (node (ref "U2") (pin "11") (pinfunction "LVOUT_11") (pintype "passive"))
      (node (ref "U4") (pin "4") (pinfunction "V+_4") (pintype "passive"))
    )
    (net (code "50") (name "unconnected-(U1-ADC6-Pad19)") (class "Default")
      (node (ref "U1") (pin "19") (pinfunction "ADC6_19") (pintype "input+no_connect"))
    )
    (net (code "51") (name "unconnected-(U1-ADC7-Pad22)") (class "Default")
      (node (ref "U1") (pin "22") (pinfunction "ADC7_22") (pintype "input+no_connect"))
    )
    (net (code "52") (name "unconnected-(U1-AREF-Pad20)") (class "Default")
      (node (ref "U1") (pin "20") (pinfunction "AREF_20") (pintype "passive+no_connect"))
    )
    (net (code "53") (name "unconnected-(U1-PB0_(PCINT0{slash}CLKO{slash}ICP1)-Pad12)") (class "Default")
      (node (ref "U1") (pin "12") (pinfunction "PB0_(PCINT0/CLKO/ICP1)_12") (pintype "bidirectional+no_connect"))
    )
    (net (code "54") (name "unconnected-(U1-PB2_(PCINT2{slash}~{SS}{slash}OC1B)-Pad14)") (class "Default")
      (node (ref "U1") (pin "14") (pinfunction "PB2_(PCINT2/~{SS}/OC1B)_14") (pintype "bidirectional"))
    )
    (net (code "55") (name "unconnected-(U1-PB6_(PCINT6{slash}XTAL1{slash}TOSC1)-Pad7)") (class "Default")
      (node (ref "U1") (pin "7") (pinfunction "PB6_(PCINT6/XTAL1/TOSC1)_7") (pintype "bidirectional+no_connect"))
    )
    (net (code "56") (name "unconnected-(U1-PB7_(PCINT7{slash}XTAL2{slash}TOSC2)-Pad8)") (class "Default")
      (node (ref "U1") (pin "8") (pinfunction "PB7_(PCINT7/XTAL2/TOSC2)_8") (pintype "bidirectional+no_connect"))
    )
    (net (code "57") (name "unconnected-(U1-PC1_(ADC1{slash}PCINT9)-Pad24)") (class "Default")
      (node (ref "U1") (pin "24") (pinfunction "PC1_(ADC1/PCINT9)_24") (pintype "bidirectional+no_connect"))
    )
    (net (code "58") (name "unconnected-(U1-PC2_(ADC2{slash}PCINT10)-Pad25)") (class "Default")
      (node (ref "U1") (pin "25") (pinfunction "PC2_(ADC2/PCINT10)_25") (pintype "bidirectional+no_connect"))
    )
    (net (code "59") (name "unconnected-(U1-PC3_(ADC3{slash}PCINT11)-Pad26)") (class "Default")
      (node (ref "U1") (pin "26") (pinfunction "PC3_(ADC3/PCINT11)_26") (pintype "bidirectional+no_connect"))
    )
    (net (code "60") (name "unconnected-(U1-PC4_(ADC4{slash}SDA{slash}PCINT12)-Pad27)") (class "Default")
      (node (ref "U1") (pin "27") (pinfunction "PC4_(ADC4/SDA/PCINT12)_27") (pintype "bidirectional+no_connect"))
    )
    (net (code "61") (name "unconnected-(U1-PC5_(ADC5{slash}SCL{slash}PCINT13)-Pad28)") (class "Default")
      (node (ref "U1") (pin "28") (pinfunction "PC5_(ADC5/SCL/PCINT13)_28") (pintype "bidirectional+no_connect"))
    )
    (net (code "62") (name "unconnected-(U1-PD5_(PCINT21{slash}OC0B{slash}T1)-Pad9)") (class "Default")
      (node (ref "U1") (pin "9") (pinfunction "PD5_(PCINT21/OC0B/T1)_9") (pintype "bidirectional+no_connect"))
    )
    (net (code "63") (name "unconnected-(U1-PD7_(PCINT23{slash}AIN1)-Pad11)") (class "Default")
      (node (ref "U1") (pin "11") (pinfunction "PD7_(PCINT23/AIN1)_11") (pintype "bidirectional"))
    )
    (net (code "64") (name "unconnected-(U4-NC-Pad1)") (class "Default")
      (node (ref "U4") (pin "1") (pinfunction "NC_1") (pintype "passive+no_connect"))
    )
  )
)
